# PLL.net
KiCad netlist of a schematic drawn in Altium Designer
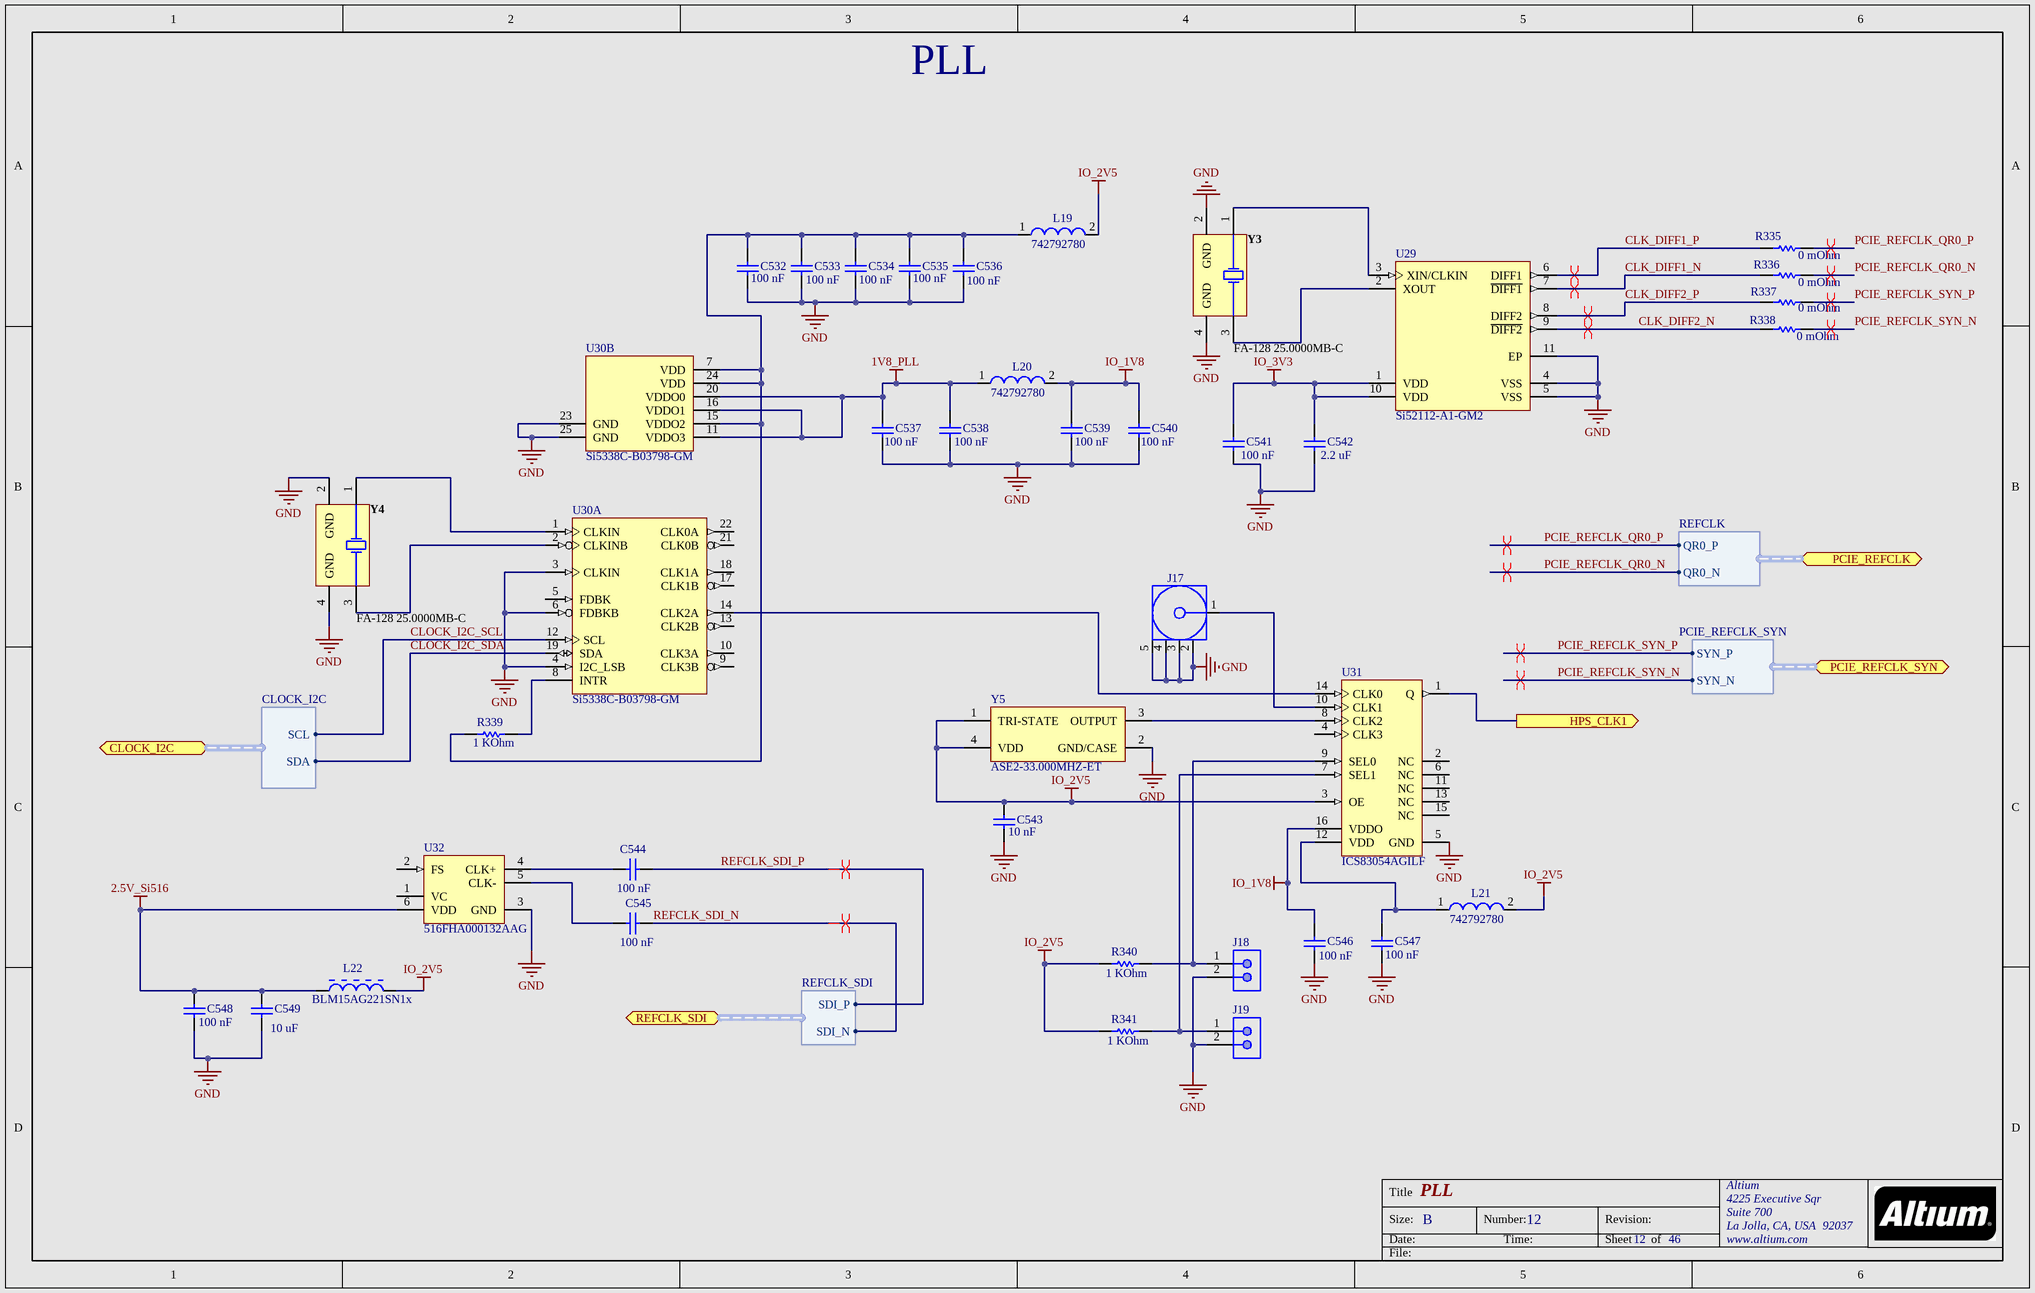
[diagram p0: PLL.SchDoc]

(export (version "E")
  (design (tool "Eeschema 10.0.6"))
  (components
    (comp (ref "C532")
      (value "C1005X7R1E104M")
      (footprint "CAPC1005X55X10LL05")
      (description "Chip Capacitor, 0.1 uF, +/- 20%, 25 V, -55 to 125 degC, 0402 (1005 Metric), RoHS, Tape and Reel")
      (fields (field (name "TOLERANCE") "20%") (field (name "CAPACITANCE") "100 nF"))
      (libsource (lib "Altium Content Vault") (part "CAP-NP-2"))
    )
    (comp (ref "C533")
      (value "C1005X7R1E104M")
      (footprint "CAPC1005X55X10LL05")
      (description "Chip Capacitor, 0.1 uF, +/- 20%, 25 V, -55 to 125 degC, 0402 (1005 Metric), RoHS, Tape and Reel")
      (fields (field (name "TOLERANCE") "20%") (field (name "CAPACITANCE") "100 nF"))
      (libsource (lib "Altium Content Vault") (part "CAP-NP-2"))
    )
    (comp (ref "C534")
      (value "C1005X7R1E104M")
      (footprint "CAPC1005X55X10LL05")
      (description "Chip Capacitor, 0.1 uF, +/- 20%, 25 V, -55 to 125 degC, 0402 (1005 Metric), RoHS, Tape and Reel")
      (fields (field (name "TOLERANCE") "20%") (field (name "CAPACITANCE") "100 nF"))
      (libsource (lib "Altium Content Vault") (part "CAP-NP-2"))
    )
    (comp (ref "C535")
      (value "C1005X7R1E104M")
      (footprint "CAPC1005X55X10LL05")
      (description "Chip Capacitor, 0.1 uF, +/- 20%, 25 V, -55 to 125 degC, 0402 (1005 Metric), RoHS, Tape and Reel")
      (fields (field (name "TOLERANCE") "20%") (field (name "CAPACITANCE") "100 nF"))
      (libsource (lib "Altium Content Vault") (part "CAP-NP-2"))
    )
    (comp (ref "C536")
      (value "C1005X7R1E104M")
      (footprint "CAPC1005X55X10LL05")
      (description "Chip Capacitor, 0.1 uF, +/- 20%, 25 V, -55 to 125 degC, 0402 (1005 Metric), RoHS, Tape and Reel")
      (fields (field (name "TOLERANCE") "20%") (field (name "CAPACITANCE") "100 nF"))
      (libsource (lib "Altium Content Vault") (part "CAP-NP-2"))
    )
    (comp (ref "C537")
      (value "C1005X7R1E104M")
      (footprint "CAPC1005X55X10LL05")
      (description "Chip Capacitor, 0.1 uF, +/- 20%, 25 V, -55 to 125 degC, 0402 (1005 Metric), RoHS, Tape and Reel")
      (fields (field (name "TOLERANCE") "20%") (field (name "CAPACITANCE") "100 nF"))
      (libsource (lib "Altium Content Vault") (part "CAP-NP-2"))
    )
    (comp (ref "C538")
      (value "C1005X7R1E104M")
      (footprint "CAPC1005X55X10LL05")
      (description "Chip Capacitor, 0.1 uF, +/- 20%, 25 V, -55 to 125 degC, 0402 (1005 Metric), RoHS, Tape and Reel")
      (fields (field (name "TOLERANCE") "20%") (field (name "CAPACITANCE") "100 nF"))
      (libsource (lib "Altium Content Vault") (part "CAP-NP-2"))
    )
    (comp (ref "C539")
      (value "C1005X7R1E104M")
      (footprint "CAPC1005X55X10LL05")
      (description "Chip Capacitor, 0.1 uF, +/- 20%, 25 V, -55 to 125 degC, 0402 (1005 Metric), RoHS, Tape and Reel")
      (fields (field (name "TOLERANCE") "20%") (field (name "CAPACITANCE") "100 nF"))
      (libsource (lib "Altium Content Vault") (part "CAP-NP-2"))
    )
    (comp (ref "C540")
      (value "C1005X7R1E104M")
      (footprint "CAPC1005X55X10LL05")
      (description "Chip Capacitor, 0.1 uF, +/- 20%, 25 V, -55 to 125 degC, 0402 (1005 Metric), RoHS, Tape and Reel")
      (fields (field (name "TOLERANCE") "20%") (field (name "CAPACITANCE") "100 nF"))
      (libsource (lib "Altium Content Vault") (part "CAP-NP-2"))
    )
    (comp (ref "C541")
      (value "C1005X7R1E104M")
      (footprint "CAPC1005X55X10LL05")
      (description "Chip Capacitor, 0.1 uF, +/- 20%, 25 V, -55 to 125 degC, 0402 (1005 Metric), RoHS, Tape and Reel")
      (fields (field (name "TOLERANCE") "20%") (field (name "CAPACITANCE") "100 nF"))
      (libsource (lib "Altium Content Vault") (part "CAP-NP-2"))
    )
    (comp (ref "C542")
      (value "GRM188R61A225KE34x")
      (footprint "CAPC1608X90X35ML10T15")
      (description "Chip Capacitor, 2.2 uF, +/- 10%, 10 V, -55 to 85 degC, 0603 (1608 Metric), RoHS, Tape and Reel")
      (fields (field (name "TOLERANCE") "10%") (field (name "CAPACITANCE") "2.2 uF"))
      (libsource (lib "") (part "CAP-NP-2_1"))
    )
    (comp (ref "C543")
      (value "GRM155R71H103KA88D")
      (footprint "CAPC1005X55X25ML05T10")
      (description "Chip Capacitor, 10 nF, +/- 10%, 50 V, -55 to 125 degC, 0402 (1005 Metric), RoHS, Tape and Reel")
      (fields
        (field (name "TOLERANCE") "10%")
        (field (name "CAPACITANCE") "10 nF")
        (field (name "MANUFACTURER") "Basic Passives")
      )
      (libsource (lib "Altium Content Vault") (part "CAP-NP-2"))
    )
    (comp (ref "C544")
      (value "C1005X7R1E104M")
      (footprint "CAPC1005X55X10LL05")
      (description "Chip Capacitor, 0.1 uF, +/- 20%, 25 V, -55 to 125 degC, 0402 (1005 Metric), RoHS, Tape and Reel")
      (fields (field (name "TOLERANCE") "20%") (field (name "CAPACITANCE") "100 nF"))
      (libsource (lib "Altium Content Vault") (part "CAP-NP-2"))
    )
    (comp (ref "C545")
      (value "C1005X7R1E104M")
      (footprint "CAPC1005X55X10LL05")
      (description "Chip Capacitor, 0.1 uF, +/- 20%, 25 V, -55 to 125 degC, 0402 (1005 Metric), RoHS, Tape and Reel")
      (fields (field (name "TOLERANCE") "20%") (field (name "CAPACITANCE") "100 nF"))
      (libsource (lib "Altium Content Vault") (part "CAP-NP-2"))
    )
    (comp (ref "C546")
      (value "C1005X7R1E104M")
      (footprint "CAPC1005X55X10LL05")
      (description "Chip Capacitor, 0.1 uF, +/- 20%, 25 V, -55 to 125 degC, 0402 (1005 Metric), RoHS, Tape and Reel")
      (fields (field (name "TOLERANCE") "20%") (field (name "CAPACITANCE") "100 nF"))
      (libsource (lib "Altium Content Vault") (part "CAP-NP-2"))
    )
    (comp (ref "C547")
      (value "C1005X7R1E104M")
      (footprint "CAPC1005X55X10LL05")
      (description "Chip Capacitor, 0.1 uF, +/- 20%, 25 V, -55 to 125 degC, 0402 (1005 Metric), RoHS, Tape and Reel")
      (fields (field (name "TOLERANCE") "20%") (field (name "CAPACITANCE") "100 nF"))
      (libsource (lib "Altium Content Vault") (part "CAP-NP-2"))
    )
    (comp (ref "C548")
      (value "C1005X7R1E104M")
      (footprint "CAPC1005X55X10LL05")
      (description "Chip Capacitor, 0.1 uF, +/- 20%, 25 V, -55 to 125 degC, 0402 (1005 Metric), RoHS, Tape and Reel")
      (fields (field (name "TOLERANCE") "20%") (field (name "CAPACITANCE") "100 nF"))
      (libsource (lib "Altium Content Vault") (part "CAP-NP-2"))
    )
    (comp (ref "C549")
      (value "C2012X5R1C106K085AC")
      (footprint "CAPC2013X100X20NL20")
      (description "Chip Capacitor, 10 uF, +/- 10%, 16 V, -55 to 85 degC, 0805 (2012 Metric), RoHS, Tape and Reel")
      (fields (field (name "TOLERANCE") "10%") (field (name "CAPACITANCE") "10 uF"))
      (libsource (lib "") (part "CAP-NP-2_1"))
    )
    (comp (ref "J17")
      (value "LTI-SASF54GT")
      (footprint "LHT-LTI-SASF54GT_V")
      (description "SMA Connector, Pitch 2.54 mm, 1 Position, Height 9.5 mm, Tail Length 4 mm, RoHS")
      (fields (field (name "MANUFACTURER") "Lighthorse Technologies Inc."))
      (libsource (lib "Altium Content Vault") (part "CMP-1713-00001-1"))
    )
    (comp (ref "J18")
      (value "613 002 111 21")
      (footprint "WE-61300211121_V")
      (fields (field (name "MANUFACTURER") "Wuerth Elektronik"))
      (libsource (lib "Altium Content Vault") (part "CMP-1712-00002-1"))
    )
    (comp (ref "J19")
      (value "613 002 111 21")
      (footprint "WE-61300211121_V")
      (fields (field (name "MANUFACTURER") "Wuerth Elektronik"))
      (libsource (lib "Altium Content Vault") (part "CMP-1712-00002-1"))
    )
    (comp (ref "L19")
      (value "742792780")
      (footprint "SMD-0402")
      (description "SMD EMI Suppression Ferrite Bead WE-CBF, Z = 220 Ohm")
      (libsource (lib "Altium Content Vault") (part "PAS-IND-INDUCTOR-2"))
    )
    (comp (ref "L20")
      (value "742792780")
      (footprint "SMD-0402")
      (description "SMD EMI Suppression Ferrite Bead WE-CBF, Z = 220 Ohm")
      (libsource (lib "Altium Content Vault") (part "CMP-0220-00137-1"))
    )
    (comp (ref "L21")
      (value "742792780")
      (footprint "SMD-0402")
      (description "SMD EMI Suppression Ferrite Bead WE-CBF, Z = 220 Ohm")
      (libsource (lib "Altium Content Vault") (part "CMP-0220-00137-1"))
    )
    (comp (ref "L22")
      (value "BLM15AG221SN1x")
      (footprint "MURA-BLM15AG221SN1x_V")
      (description "Chip Bead, 220 Ohm, +/- 25 %, 100 MHz, 300 mA, -55 to 125 degC, 0402 (1005 Metric), RoHS")
      (fields (field (name "TOLERANCE") "25%"))
      (libsource (lib "Altium Content Vault") (part "BEAD-2"))
    )
    (comp (ref "R335")
      (value "ERJ-2GE0R00X")
      (footprint "RESC1005X40X25ML05T05")
      (description "Chip Resistor, 0 mOhm, +/- 5%, 100 mW, -55 to 155 degC, 0402 (1005 Metric), RoHS, Tape and Reel")
      (fields
        (field (name "TOLERANCE") "5%")
        (field (name "RESISTANCE") "0 mOhm")
        (field (name "MANUFACTURER") "Basic Passives")
      )
      (libsource (lib "Altium Content Vault") (part "RES-2"))
    )
    (comp (ref "R336")
      (value "ERJ-2GE0R00X")
      (footprint "RESC1005X40X25ML05T05")
      (description "Chip Resistor, 0 mOhm, +/- 5%, 100 mW, -55 to 155 degC, 0402 (1005 Metric), RoHS, Tape and Reel")
      (fields
        (field (name "TOLERANCE") "5%")
        (field (name "RESISTANCE") "0 mOhm")
        (field (name "MANUFACTURER") "Basic Passives")
      )
      (libsource (lib "Altium Content Vault") (part "RES-2"))
    )
    (comp (ref "R337")
      (value "ERJ-2GE0R00X")
      (footprint "RESC1005X40X25ML05T05")
      (description "Chip Resistor, 0 mOhm, +/- 5%, 100 mW, -55 to 155 degC, 0402 (1005 Metric), RoHS, Tape and Reel")
      (fields
        (field (name "TOLERANCE") "5%")
        (field (name "RESISTANCE") "0 mOhm")
        (field (name "MANUFACTURER") "Basic Passives")
      )
      (libsource (lib "Altium Content Vault") (part "RES-2"))
    )
    (comp (ref "R338")
      (value "ERJ-2GE0R00X")
      (footprint "RESC1005X40X25ML05T05")
      (description "Chip Resistor, 0 mOhm, +/- 5%, 100 mW, -55 to 155 degC, 0402 (1005 Metric), RoHS, Tape and Reel")
      (fields
        (field (name "TOLERANCE") "5%")
        (field (name "RESISTANCE") "0 mOhm")
        (field (name "MANUFACTURER") "Basic Passives")
      )
      (libsource (lib "Altium Content Vault") (part "RES-2"))
    )
    (comp (ref "R339")
      (value "ERJ-2RKF1001X")
      (footprint "RESC1005X40X25LL05T05")
      (description "Chip Resistor, 1 KOhm, +/- 1%, 100 mW, -55 to 155 degC, 0402 (1005 Metric), RoHS, Tape and Reel")
      (fields
        (field (name "RESISTANCE") "1 KOhm")
        (field (name "TOLERANCE") "1%")
        (field (name "MANUFACTURER") "Basic Passives")
      )
      (libsource (lib "Altium Content Vault") (part "RES-2"))
    )
    (comp (ref "R340")
      (value "ERJ-2RKF1001X")
      (footprint "RESC1005X40X25LL05T05")
      (description "Chip Resistor, 1 KOhm, +/- 1%, 100 mW, -55 to 155 degC, 0402 (1005 Metric), RoHS, Tape and Reel")
      (fields
        (field (name "RESISTANCE") "1 KOhm")
        (field (name "TOLERANCE") "1%")
        (field (name "MANUFACTURER") "Basic Passives")
      )
      (libsource (lib "Altium Content Vault") (part "RES-2"))
    )
    (comp (ref "R341")
      (value "ERJ-2RKF1001X")
      (footprint "RESC1005X40X25LL05T05")
      (description "Chip Resistor, 1 KOhm, +/- 1%, 100 mW, -55 to 155 degC, 0402 (1005 Metric), RoHS, Tape and Reel")
      (fields
        (field (name "RESISTANCE") "1 KOhm")
        (field (name "TOLERANCE") "1%")
        (field (name "MANUFACTURER") "Basic Passives")
      )
      (libsource (lib "Altium Content Vault") (part "RES-2"))
    )
    (comp (ref "U29")
      (value "Si52112-A1-GM2")
      (footprint "SLAB-TDFN-10_L")
      (fields (field (name "MANUFACTURER") "Silicon Labs"))
      (libsource (lib "Altium Content Vault") (part "CMP-1706-00007-1"))
    )
    (comp (ref "U30")
      (value "Si5338C-B03798-GM")
      (footprint "SLAB-QFN-24-2550x2550TP_V")
      (fields (field (name "MANUFACTURER") "Silicon Labs"))
      (libsource (lib "Altium Content Vault") (part "CMP-1706-00005-1"))
    )
    (comp (ref "U31")
      (value "ICS83054AGILF")
      (footprint "IDT-TSSOP-16_M")
      (description "Single-Ended Multiplexer, 2.375 to 3.465 V, -40 to 85 degC, 16-Pin TSSOP, RoHS, Tube")
      (fields (field (name "MANUFACTURER") "IDT"))
      (libsource (lib "Altium Content Vault") (part "CMP-1699-00001-1"))
    )
    (comp (ref "U32")
      (value "516FHA000132AAG")
      (footprint "SLAB-DFN-6-5000X7000DE_A_V")
      (fields (field (name "MANUFACTURER") "Silicon Labs"))
      (libsource (lib "Altium Content Vault") (part "CMP-1706-00001-1"))
    )
    (comp (ref "Y3")
      (value "FA-128 25.0000MB-C")
      (footprint "EPSON-FA-128_V")
      (description "Range Crystal Unit, 25 MHz, -40 to 85 degC, 4-Pin SMD, RoHS, Tape and Reel")
      (libsource (lib "Altium Content Vault") (part "XTAL-1-3-4"))
    )
    (comp (ref "Y4")
      (value "FA-128 25.0000MB-C")
      (footprint "EPSON-FA-128_V")
      (description "Range Crystal Unit, 25 MHz, -40 to 85 degC, 4-Pin SMD, RoHS, Tape and Reel")
      (libsource (lib "Altium Content Vault") (part "XTAL-1-3-4"))
    )
    (comp (ref "Y5")
      (value "ASE2-33.000MHZ-ET")
      (footprint "ABRA-ASE2_V")
      (fields (field (name "MANUFACTURER") "Abracon"))
      (libsource (lib "Altium Content Vault") (part "CMP-1688-00001-1"))
    )
  )
  (nets
    (net (code "5") (name "/CLK_DIFF1_N") (class "Default")
      (node (ref "R336") (pin "1") (pinfunction "1_1") (pintype "passive"))
      (node (ref "U29") (pin "7") (pinfunction "~{DIFF1}_7") (pintype "output"))
    )
    (net (code "6") (name "/CLK_DIFF1_P") (class "Default")
      (node (ref "R335") (pin "1") (pinfunction "1_1") (pintype "passive"))
      (node (ref "U29") (pin "6") (pinfunction "DIFF1_6") (pintype "output"))
    )
    (net (code "7") (name "/CLK_DIFF2_N") (class "Default")
      (node (ref "R338") (pin "1") (pinfunction "1_1") (pintype "passive"))
      (node (ref "U29") (pin "9") (pinfunction "~{DIFF2}_9") (pintype "output"))
    )
    (net (code "8") (name "/CLK_DIFF2_P") (class "Default")
      (node (ref "R337") (pin "1") (pinfunction "1_1") (pintype "passive"))
      (node (ref "U29") (pin "8") (pinfunction "DIFF2_8") (pintype "output"))
    )
    (net (code "9") (name "/CLOCK_I2C_SCL") (class "Default")
      (node (ref "U30") (pin "12") (pinfunction "SCL_12") (pintype "input"))
    )
    (net (code "10") (name "/CLOCK_I2C_SDA") (class "Default")
      (node (ref "U30") (pin "19") (pinfunction "SDA_19") (pintype "bidirectional"))
    )
    (net (code "11") (name "/HPS_CLK1") (class "Default")
      (node (ref "U31") (pin "1") (pinfunction "Q_1") (pintype "output"))
    )
    (net (code "12") (name "/PCIE_REFCLK_QR0_N") (class "Default")
      (node (ref "R336") (pin "2") (pinfunction "2_2") (pintype "passive"))
    )
    (net (code "13") (name "/PCIE_REFCLK_QR0_P") (class "Default")
      (node (ref "R335") (pin "2") (pinfunction "2_2") (pintype "passive"))
    )
    (net (code "14") (name "/PCIE_REFCLK_SYN_N") (class "Default")
      (node (ref "R338") (pin "2") (pinfunction "2_2") (pintype "passive"))
    )
    (net (code "15") (name "/PCIE_REFCLK_SYN_P") (class "Default")
      (node (ref "R337") (pin "2") (pinfunction "2_2") (pintype "passive"))
    )
    (net (code "16") (name "/REFCLK_SDI_N") (class "Default")
      (node (ref "C545") (pin "1") (pinfunction "1_1") (pintype "passive"))
    )
    (net (code "17") (name "/REFCLK_SDI_P") (class "Default")
      (node (ref "C544") (pin "1") (pinfunction "1_1") (pintype "passive"))
    )
    (net (code "22") (name "1V8_PLL") (class "Default")
      (node (ref "C537") (pin "2") (pinfunction "2_2") (pintype "passive"))
      (node (ref "C538") (pin "2") (pinfunction "2_2") (pintype "passive"))
      (node (ref "L20") (pin "1") (pinfunction "1_1") (pintype "passive"))
      (node (ref "U30") (pin "11") (pinfunction "VDDO3_11") (pintype "power_in"))
      (node (ref "U30") (pin "16") (pinfunction "VDDO1_16") (pintype "power_in"))
      (node (ref "U30") (pin "20") (pinfunction "VDDO0_20") (pintype "power_in"))
    )
    (net (code "23") (name "2.5V_Si516") (class "Default")
      (node (ref "C548") (pin "2") (pinfunction "2_2") (pintype "passive"))
      (node (ref "C549") (pin "2") (pinfunction "2_2") (pintype "passive"))
      (node (ref "L22") (pin "1") (pinfunction "1_1") (pintype "passive"))
      (node (ref "U32") (pin "6") (pinfunction "VDD_6") (pintype "power_in"))
    )
    (net (code "24") (name "GND") (class "Default")
      (node (ref "C532") (pin "1") (pinfunction "1_1") (pintype "passive"))
      (node (ref "C533") (pin "1") (pinfunction "1_1") (pintype "passive"))
      (node (ref "C534") (pin "1") (pinfunction "1_1") (pintype "passive"))
      (node (ref "C535") (pin "1") (pinfunction "1_1") (pintype "passive"))
      (node (ref "C536") (pin "1") (pinfunction "1_1") (pintype "passive"))
      (node (ref "C537") (pin "1") (pinfunction "1_1") (pintype "passive"))
      (node (ref "C538") (pin "1") (pinfunction "1_1") (pintype "passive"))
      (node (ref "C539") (pin "1") (pinfunction "1_1") (pintype "passive"))
      (node (ref "C540") (pin "1") (pinfunction "1_1") (pintype "passive"))
      (node (ref "C541") (pin "1") (pinfunction "1_1") (pintype "passive"))
      (node (ref "C542") (pin "1") (pinfunction "1_1") (pintype "passive"))
      (node (ref "C543") (pin "1") (pinfunction "1_1") (pintype "passive"))
      (node (ref "C546") (pin "1") (pinfunction "1_1") (pintype "passive"))
      (node (ref "C547") (pin "1") (pinfunction "1_1") (pintype "passive"))
      (node (ref "C548") (pin "1") (pinfunction "1_1") (pintype "passive"))
      (node (ref "C549") (pin "1") (pinfunction "1_1") (pintype "passive"))
      (node (ref "J17") (pin "2") (pinfunction "2_2") (pintype "passive"))
      (node (ref "J17") (pin "3") (pinfunction "3_3") (pintype "passive"))
      (node (ref "J17") (pin "4") (pinfunction "4_4") (pintype "passive"))
      (node (ref "J17") (pin "5") (pinfunction "5_5") (pintype "passive"))
      (node (ref "J18") (pin "2") (pinfunction "2_2") (pintype "passive"))
      (node (ref "J19") (pin "2") (pinfunction "2_2") (pintype "passive"))
      (node (ref "U29") (pin "11") (pinfunction "EP_11") (pintype "passive"))
      (node (ref "U29") (pin "4") (pinfunction "VSS_4") (pintype "power_in"))
      (node (ref "U29") (pin "5") (pinfunction "VSS_5") (pintype "power_in"))
      (node (ref "U30") (pin "23") (pinfunction "GND_23") (pintype "power_in"))
      (node (ref "U30") (pin "25") (pinfunction "GND_25") (pintype "power_in"))
      (node (ref "U30") (pin "3") (pinfunction "CLKIN_3") (pintype "input"))
      (node (ref "U30") (pin "4") (pinfunction "I2C_LSB_4") (pintype "input"))
      (node (ref "U30") (pin "6") (pinfunction "FDBKB_6") (pintype "input"))
      (node (ref "U31") (pin "5") (pinfunction "GND_5") (pintype "power_in"))
      (node (ref "U32") (pin "3") (pinfunction "GND_3") (pintype "power_in"))
      (node (ref "Y3") (pin "2") (pinfunction "GND_2") (pintype "power_in"))
      (node (ref "Y3") (pin "4") (pinfunction "GND_4") (pintype "power_in"))
      (node (ref "Y4") (pin "2") (pinfunction "GND_2") (pintype "power_in"))
      (node (ref "Y4") (pin "4") (pinfunction "GND_4") (pintype "power_in"))
      (node (ref "Y5") (pin "2") (pinfunction "GND/CASE_2") (pintype "power_in"))
    )
    (net (code "25") (name "IO_1V8") (class "Default")
      (node (ref "C539") (pin "2") (pinfunction "2_2") (pintype "passive"))
      (node (ref "C540") (pin "2") (pinfunction "2_2") (pintype "passive"))
      (node (ref "C546") (pin "2") (pinfunction "2_2") (pintype "passive"))
      (node (ref "L20") (pin "2") (pinfunction "2_2") (pintype "passive"))
      (node (ref "U31") (pin "16") (pinfunction "VDDO_16") (pintype "power_in"))
    )
    (net (code "26") (name "IO_2V5") (class "Default")
      (node (ref "C543") (pin "2") (pinfunction "2_2") (pintype "passive"))
      (node (ref "L19") (pin "2") (pinfunction "2_2") (pintype "passive"))
      (node (ref "L21") (pin "2") (pinfunction "2_2") (pintype "passive"))
      (node (ref "L22") (pin "2") (pinfunction "2_2") (pintype "passive"))
      (node (ref "R340") (pin "1") (pinfunction "1_1") (pintype "passive"))
      (node (ref "R341") (pin "1") (pinfunction "1_1") (pintype "passive"))
      (node (ref "U31") (pin "3") (pinfunction "OE_3") (pintype "input"))
      (node (ref "Y5") (pin "1") (pinfunction "TRI-STATE_1") (pintype "passive"))
      (node (ref "Y5") (pin "4") (pinfunction "VDD_4") (pintype "power_in"))
    )
    (net (code "27") (name "IO_3V3") (class "Default")
      (node (ref "C541") (pin "2") (pinfunction "2_2") (pintype "passive"))
      (node (ref "C542") (pin "2") (pinfunction "2_2") (pintype "passive"))
      (node (ref "U29") (pin "1") (pinfunction "VDD_1") (pintype "power_in"))
      (node (ref "U29") (pin "10") (pinfunction "VDD_10") (pintype "power_in"))
    )
    (net (code "28") (name "Net-(U29-XIN{slash}CLKIN)") (class "Default")
      (node (ref "U29") (pin "3") (pinfunction "XIN/CLKIN_3") (pintype "input"))
      (node (ref "Y3") (pin "1") (pinfunction "X1_1") (pintype "passive"))
    )
    (net (code "29") (name "Net-(U29-XOUT)") (class "Default")
      (node (ref "U29") (pin "2") (pinfunction "XOUT_2") (pintype "passive"))
      (node (ref "Y3") (pin "3") (pinfunction "X2_3") (pintype "passive"))
    )
    (net (code "30") (name "Net-(U30A-CLK2A)") (class "Default")
      (node (ref "U30") (pin "14") (pinfunction "CLK2A_14") (pintype "output"))
      (node (ref "U31") (pin "14") (pinfunction "CLK0_14") (pintype "input"))
    )
    (net (code "31") (name "Net-(U30A-CLKINB)") (class "Default")
      (node (ref "U30") (pin "2") (pinfunction "CLKINB_2") (pintype "input"))
      (node (ref "Y4") (pin "3") (pinfunction "X2_3") (pintype "passive"))
    )
    (net (code "32") (name "Net-(U30A-INTR)") (class "Default")
      (node (ref "R339") (pin "2") (pinfunction "2_2") (pintype "passive"))
      (node (ref "U30") (pin "8") (pinfunction "INTR_8") (pintype "open_collector"))
    )
    (net (code "33") (name "Net-(U30B-VDDO2)") (class "Default")
      (node (ref "C532") (pin "2") (pinfunction "2_2") (pintype "passive"))
      (node (ref "C533") (pin "2") (pinfunction "2_2") (pintype "passive"))
      (node (ref "C534") (pin "2") (pinfunction "2_2") (pintype "passive"))
      (node (ref "C535") (pin "2") (pinfunction "2_2") (pintype "passive"))
      (node (ref "C536") (pin "2") (pinfunction "2_2") (pintype "passive"))
      (node (ref "L19") (pin "1") (pinfunction "1_1") (pintype "passive"))
      (node (ref "R339") (pin "1") (pinfunction "1_1") (pintype "passive"))
      (node (ref "U30") (pin "15") (pinfunction "VDDO2_15") (pintype "power_in"))
      (node (ref "U30") (pin "24") (pinfunction "VDD_24") (pintype "power_in"))
      (node (ref "U30") (pin "7") (pinfunction "VDD_7") (pintype "power_in"))
    )
    (net (code "34") (name "Net-(U31-CLK1)") (class "Default")
      (node (ref "J17") (pin "1") (pinfunction "1_1") (pintype "passive"))
      (node (ref "U31") (pin "10") (pinfunction "CLK1_10") (pintype "input"))
    )
    (net (code "35") (name "Net-(U31-CLK2)") (class "Default")
      (node (ref "U31") (pin "8") (pinfunction "CLK2_8") (pintype "input"))
      (node (ref "Y5") (pin "3") (pinfunction "OUTPUT_3") (pintype "passive"))
    )
    (net (code "36") (name "Net-(U31-SEL0)") (class "Default")
      (node (ref "J18") (pin "1") (pinfunction "1_1") (pintype "passive"))
      (node (ref "R340") (pin "2") (pinfunction "2_2") (pintype "passive"))
      (node (ref "U31") (pin "9") (pinfunction "SEL0_9") (pintype "input"))
    )
    (net (code "37") (name "Net-(U31-SEL1)") (class "Default")
      (node (ref "J19") (pin "1") (pinfunction "1_1") (pintype "passive"))
      (node (ref "R341") (pin "2") (pinfunction "2_2") (pintype "passive"))
      (node (ref "U31") (pin "7") (pinfunction "SEL1_7") (pintype "input"))
    )
    (net (code "38") (name "Net-(U31-VDD)") (class "Default")
      (node (ref "C547") (pin "2") (pinfunction "2_2") (pintype "passive"))
      (node (ref "L21") (pin "1") (pinfunction "1_1") (pintype "passive"))
      (node (ref "U31") (pin "12") (pinfunction "VDD_12") (pintype "power_in"))
    )
    (net (code "39") (name "Net-(U32-CLK+)") (class "Default")
      (node (ref "C544") (pin "2") (pinfunction "2_2") (pintype "passive"))
      (node (ref "U32") (pin "4") (pinfunction "CLK+_4") (pintype "tri_state"))
    )
    (net (code "40") (name "Net-(U32-CLK-)") (class "Default")
      (node (ref "C545") (pin "2") (pinfunction "2_2") (pintype "passive"))
      (node (ref "U32") (pin "5") (pinfunction "CLK-_5") (pintype "tri_state"))
    )
    (net (code "41") (name "Net-(Y4-X1)") (class "Default")
      (node (ref "U30") (pin "1") (pinfunction "CLKIN_1") (pintype "input"))
      (node (ref "Y4") (pin "1") (pinfunction "X1_1") (pintype "passive"))
    )
    (net (code "42") (name "unconnected-(U30A-CLK0A-Pad22)") (class "Default")
      (node (ref "U30") (pin "22") (pinfunction "CLK0A_22") (pintype "output"))
    )
    (net (code "43") (name "unconnected-(U30A-CLK0B-Pad21)") (class "Default")
      (node (ref "U30") (pin "21") (pinfunction "CLK0B_21") (pintype "output"))
    )
    (net (code "44") (name "unconnected-(U30A-CLK1A-Pad18)") (class "Default")
      (node (ref "U30") (pin "18") (pinfunction "CLK1A_18") (pintype "output"))
    )
    (net (code "45") (name "unconnected-(U30A-CLK1B-Pad17)") (class "Default")
      (node (ref "U30") (pin "17") (pinfunction "CLK1B_17") (pintype "output"))
    )
    (net (code "46") (name "unconnected-(U30A-CLK2B-Pad13)") (class "Default")
      (node (ref "U30") (pin "13") (pinfunction "CLK2B_13") (pintype "output"))
    )
    (net (code "47") (name "unconnected-(U30A-CLK3A-Pad10)") (class "Default")
      (node (ref "U30") (pin "10") (pinfunction "CLK3A_10") (pintype "output"))
    )
    (net (code "48") (name "unconnected-(U30A-CLK3B-Pad9)") (class "Default")
      (node (ref "U30") (pin "9") (pinfunction "CLK3B_9") (pintype "output"))
    )
    (net (code "49") (name "unconnected-(U30A-FDBK-Pad5)") (class "Default")
      (node (ref "U30") (pin "5") (pinfunction "FDBK_5") (pintype "input"))
    )
    (net (code "50") (name "unconnected-(U31-CLK3-Pad4)") (class "Default")
      (node (ref "U31") (pin "4") (pinfunction "CLK3_4") (pintype "input"))
    )
    (net (code "51") (name "unconnected-(U31-NC-Pad2)") (class "Default")
      (node (ref "U31") (pin "2") (pinfunction "NC_2") (pintype "passive"))
    )
    (net (code "52") (name "unconnected-(U31-NC-Pad6)") (class "Default")
      (node (ref "U31") (pin "6") (pinfunction "NC_6") (pintype "passive"))
    )
    (net (code "53") (name "unconnected-(U31-NC-Pad11)") (class "Default")
      (node (ref "U31") (pin "11") (pinfunction "NC_11") (pintype "passive"))
    )
    (net (code "54") (name "unconnected-(U31-NC-Pad13)") (class "Default")
      (node (ref "U31") (pin "13") (pinfunction "NC_13") (pintype "passive"))
    )
    (net (code "55") (name "unconnected-(U31-NC-Pad15)") (class "Default")
      (node (ref "U31") (pin "15") (pinfunction "NC_15") (pintype "passive"))
    )
    (net (code "56") (name "unconnected-(U32-FS-Pad2)") (class "Default")
      (node (ref "U32") (pin "2") (pinfunction "FS_2") (pintype "input"))
    )
    (net (code "57") (name "unconnected-(U32-VC-Pad1)") (class "Default")
      (node (ref "U32") (pin "1") (pinfunction "VC_1") (pintype "power_in"))
    )
  )
)
